# Highdriver.net
KiCad netlist of a schematic drawn in Altium Designer
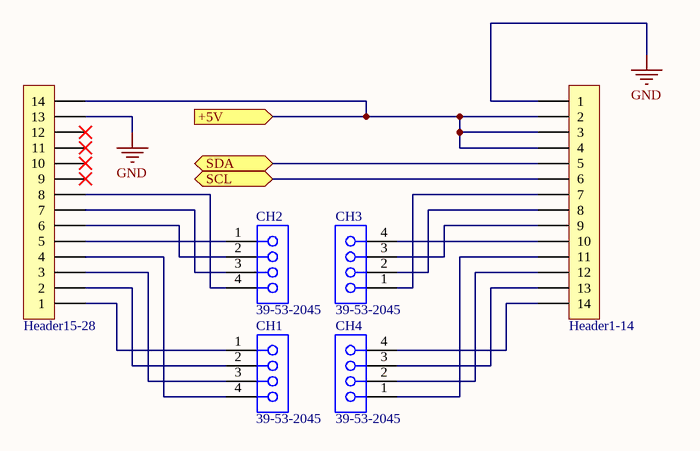
[diagram p0: Highdriver.SchDoc]

(export (version "E")
  (design (tool "Eeschema 10.0.6"))
  (components
    (comp (ref "CH1")
      (value "39-53-2045")
      (footprint "MOLX-39-53-2045")
      (fields (field (name "MANUFACTURER") "Molex"))
      (libsource (lib "") (part "MOLX-39-53-2045_1"))
    )
    (comp (ref "CH2")
      (value "39-53-2045")
      (footprint "MOLX-39-53-2045")
      (fields (field (name "MANUFACTURER") "Molex"))
      (libsource (lib "") (part "MOLX-39-53-2045_1"))
    )
    (comp (ref "CH3")
      (value "39-53-2045")
      (footprint "MOLX-39-53-2045")
      (fields (field (name "MANUFACTURER") "Molex"))
      (libsource (lib "Altium Content Vault") (part "MOLX-39-53-2045"))
    )
    (comp (ref "CH4")
      (value "39-53-2045")
      (footprint "MOLX-39-53-2045")
      (fields (field (name "MANUFACTURER") "Molex"))
      (libsource (lib "Altium Content Vault") (part "MOLX-39-53-2045"))
    )
    (comp (ref "Header1-14")
      (value "PH1x14")
      (footprint "PH2,54mm-1x14")
      (fields (field (name "PART NUMBER") "PH2,54mm-1x14"))
      (libsource (lib "") (part "PH1x14_1"))
    )
    (comp (ref "Header15-28")
      (value "PH1x14")
      (footprint "PH2,54mm-1x14")
      (fields (field (name "PART NUMBER") "PH2,54mm-1x14"))
      (libsource (lib "LTE_altium") (part "PH1x14"))
    )
  )
  (nets
    (net (code "1") (name "/+5V") (class "Default")
      (node (ref "Header1-14") (pin "2") (pinfunction "2_2") (pintype "passive"))
      (node (ref "Header1-14") (pin "3") (pinfunction "3_3") (pintype "passive"))
      (node (ref "Header1-14") (pin "4") (pinfunction "4_4") (pintype "passive"))
      (node (ref "Header15-28") (pin "14") (pinfunction "14_14") (pintype "passive"))
    )
    (net (code "2") (name "/SCL") (class "Default")
      (node (ref "Header1-14") (pin "6") (pinfunction "6_6") (pintype "passive"))
    )
    (net (code "3") (name "/SDA") (class "Default")
      (node (ref "Header1-14") (pin "5") (pinfunction "5_5") (pintype "passive"))
    )
    (net (code "4") (name "GND") (class "Default")
      (node (ref "Header1-14") (pin "1") (pinfunction "1_1") (pintype "passive"))
      (node (ref "Header15-28") (pin "13") (pinfunction "13_13") (pintype "passive"))
    )
    (net (code "5") (name "Net-(CH1-Pad1)") (class "Default")
      (node (ref "CH1") (pin "1") (pinfunction "1_1") (pintype "passive"))
      (node (ref "Header15-28") (pin "1") (pinfunction "1_1") (pintype "passive"))
    )
    (net (code "6") (name "Net-(CH1-Pad2)") (class "Default")
      (node (ref "CH1") (pin "2") (pinfunction "2_2") (pintype "passive"))
      (node (ref "Header15-28") (pin "2") (pinfunction "2_2") (pintype "passive"))
    )
    (net (code "7") (name "Net-(CH1-Pad3)") (class "Default")
      (node (ref "CH1") (pin "3") (pinfunction "3_3") (pintype "passive"))
      (node (ref "Header15-28") (pin "3") (pinfunction "3_3") (pintype "passive"))
    )
    (net (code "8") (name "Net-(CH1-Pad4)") (class "Default")
      (node (ref "CH1") (pin "4") (pinfunction "4_4") (pintype "passive"))
      (node (ref "Header15-28") (pin "4") (pinfunction "4_4") (pintype "passive"))
    )
    (net (code "9") (name "Net-(CH2-Pad1)") (class "Default")
      (node (ref "CH2") (pin "1") (pinfunction "1_1") (pintype "passive"))
      (node (ref "Header15-28") (pin "5") (pinfunction "5_5") (pintype "passive"))
    )
    (net (code "10") (name "Net-(CH2-Pad2)") (class "Default")
      (node (ref "CH2") (pin "2") (pinfunction "2_2") (pintype "passive"))
      (node (ref "Header15-28") (pin "6") (pinfunction "6_6") (pintype "passive"))
    )
    (net (code "11") (name "Net-(CH2-Pad3)") (class "Default")
      (node (ref "CH2") (pin "3") (pinfunction "3_3") (pintype "passive"))
      (node (ref "Header15-28") (pin "7") (pinfunction "7_7") (pintype "passive"))
    )
    (net (code "12") (name "Net-(CH2-Pad4)") (class "Default")
      (node (ref "CH2") (pin "4") (pinfunction "4_4") (pintype "passive"))
      (node (ref "Header15-28") (pin "8") (pinfunction "8_8") (pintype "passive"))
    )
    (net (code "13") (name "Net-(CH3-Pad1)") (class "Default")
      (node (ref "CH3") (pin "1") (pinfunction "1_1") (pintype "passive"))
      (node (ref "Header1-14") (pin "7") (pinfunction "7_7") (pintype "passive"))
    )
    (net (code "14") (name "Net-(CH3-Pad2)") (class "Default")
      (node (ref "CH3") (pin "2") (pinfunction "2_2") (pintype "passive"))
      (node (ref "Header1-14") (pin "8") (pinfunction "8_8") (pintype "passive"))
    )
    (net (code "15") (name "Net-(CH3-Pad3)") (class "Default")
      (node (ref "CH3") (pin "3") (pinfunction "3_3") (pintype "passive"))
      (node (ref "Header1-14") (pin "9") (pinfunction "9_9") (pintype "passive"))
    )
    (net (code "16") (name "Net-(CH3-Pad4)") (class "Default")
      (node (ref "CH3") (pin "4") (pinfunction "4_4") (pintype "passive"))
      (node (ref "Header1-14") (pin "10") (pinfunction "10_10") (pintype "passive"))
    )
    (net (code "17") (name "Net-(CH4-Pad1)") (class "Default")
      (node (ref "CH4") (pin "1") (pinfunction "1_1") (pintype "passive"))
      (node (ref "Header1-14") (pin "11") (pinfunction "11_11") (pintype "passive"))
    )
    (net (code "18") (name "Net-(CH4-Pad2)") (class "Default")
      (node (ref "CH4") (pin "2") (pinfunction "2_2") (pintype "passive"))
      (node (ref "Header1-14") (pin "12") (pinfunction "12_12") (pintype "passive"))
    )
    (net (code "19") (name "Net-(CH4-Pad3)") (class "Default")
      (node (ref "CH4") (pin "3") (pinfunction "3_3") (pintype "passive"))
      (node (ref "Header1-14") (pin "13") (pinfunction "13_13") (pintype "passive"))
    )
    (net (code "20") (name "Net-(CH4-Pad4)") (class "Default")
      (node (ref "CH4") (pin "4") (pinfunction "4_4") (pintype "passive"))
      (node (ref "Header1-14") (pin "14") (pinfunction "14_14") (pintype "passive"))
    )
    (net (code "21") (name "unconnected-(Header15-28-Pad9)") (class "Default")
      (node (ref "Header15-28") (pin "9") (pinfunction "9_9") (pintype "passive+no_connect"))
    )
    (net (code "22") (name "unconnected-(Header15-28-Pad10)") (class "Default")
      (node (ref "Header15-28") (pin "10") (pinfunction "10_10") (pintype "passive+no_connect"))
    )
    (net (code "23") (name "unconnected-(Header15-28-Pad11)") (class "Default")
      (node (ref "Header15-28") (pin "11") (pinfunction "11_11") (pintype "passive+no_connect"))
    )
    (net (code "24") (name "unconnected-(Header15-28-Pad12)") (class "Default")
      (node (ref "Header15-28") (pin "12") (pinfunction "12_12") (pintype "passive+no_connect"))
    )
  )
)
